# Chip_Tester.net
KiCad netlist of a schematic drawn in Altium Designer
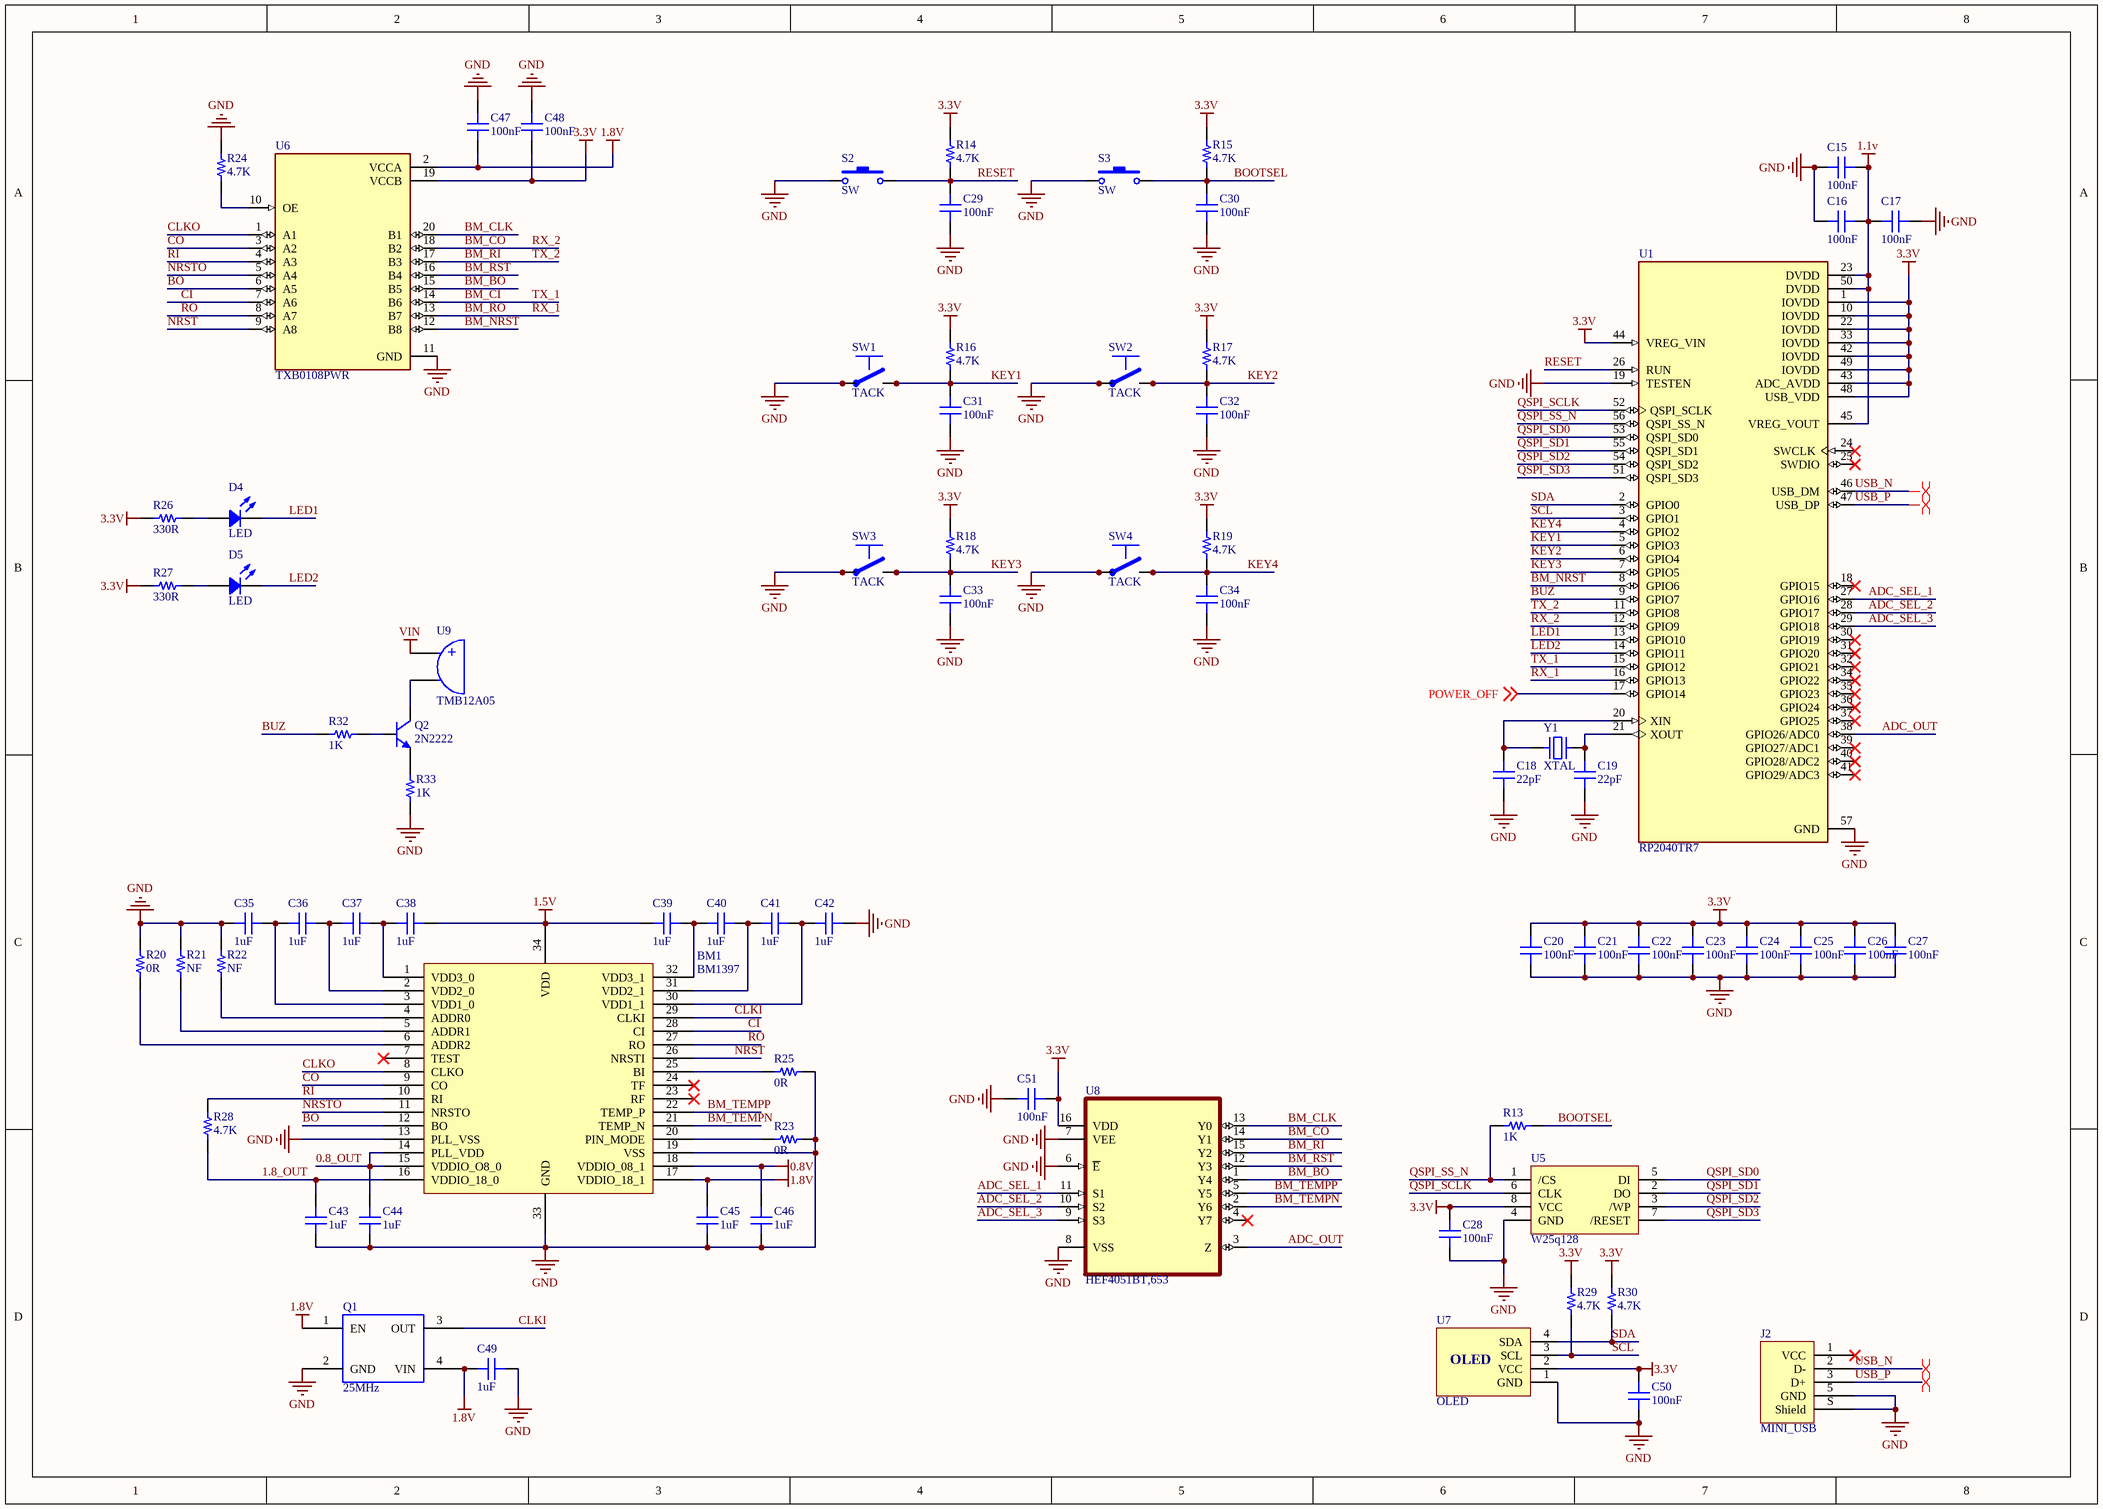
[diagram p0: Chip_Tester.SchDoc]

(export (version "E")
  (design (tool "Eeschema 10.0.6"))
  (components
    (comp (ref "BM1")
      (value "BM1397")
      (footprint "AllSocket")
      (libsource (lib "Chip_Tester") (part "BM1397_0"))
    )
    (comp (ref "C15") (value "100nF") (footprint "CAP_SMD_0805") (libsource (lib "Chip_Tester") (part "CAP")))
    (comp (ref "C16") (value "100nF") (footprint "CAP_SMD_0805") (libsource (lib "Chip_Tester") (part "CAP")))
    (comp (ref "C17") (value "100nF") (footprint "CAP_SMD_0805") (libsource (lib "Chip_Tester") (part "CAP")))
    (comp (ref "C18") (value "22pF") (footprint "CAP_SMD_0805") (libsource (lib "Chip_Tester") (part "CAP")))
    (comp (ref "C19") (value "22pF") (footprint "CAP_SMD_0805") (libsource (lib "Chip_Tester") (part "CAP")))
    (comp (ref "C20") (value "100nF") (footprint "CAP_SMD_0805") (libsource (lib "Chip_Tester") (part "CAP")))
    (comp (ref "C21") (value "100nF") (footprint "CAP_SMD_0805") (libsource (lib "Chip_Tester") (part "CAP")))
    (comp (ref "C22") (value "100nF") (footprint "CAP_SMD_0805") (libsource (lib "Chip_Tester") (part "CAP")))
    (comp (ref "C23") (value "100nF") (footprint "CAP_SMD_0805") (libsource (lib "Chip_Tester") (part "CAP")))
    (comp (ref "C24") (value "100nF") (footprint "CAP_SMD_0805") (libsource (lib "Chip_Tester") (part "CAP")))
    (comp (ref "C25") (value "100nF") (footprint "CAP_SMD_0805") (libsource (lib "Chip_Tester") (part "CAP")))
    (comp (ref "C26") (value "100nF") (footprint "CAP_SMD_0805") (libsource (lib "Chip_Tester") (part "CAP")))
    (comp (ref "C27") (value "100nF") (footprint "CAP_SMD_0805") (libsource (lib "Chip_Tester") (part "CAP")))
    (comp (ref "C28") (value "100nF") (footprint "CAP_SMD_0805") (libsource (lib "Chip_Tester") (part "CAP")))
    (comp (ref "C29") (value "100nF") (footprint "CAP_SMD_0805") (libsource (lib "Chip_Tester") (part "CAP")))
    (comp (ref "C30") (value "100nF") (footprint "CAP_SMD_0805") (libsource (lib "Chip_Tester") (part "CAP")))
    (comp (ref "C31") (value "100nF") (footprint "CAP_SMD_0805") (libsource (lib "Chip_Tester") (part "CAP")))
    (comp (ref "C32") (value "100nF") (footprint "CAP_SMD_0805") (libsource (lib "Chip_Tester") (part "CAP")))
    (comp (ref "C33") (value "100nF") (footprint "CAP_SMD_0805") (libsource (lib "Chip_Tester") (part "CAP")))
    (comp (ref "C34") (value "100nF") (footprint "CAP_SMD_0805") (libsource (lib "Chip_Tester") (part "CAP")))
    (comp (ref "C35") (value "1uF") (footprint "CAP_SMD_0805") (libsource (lib "Chip_Tester") (part "CAP")))
    (comp (ref "C36") (value "1uF") (footprint "CAP_SMD_0805") (libsource (lib "Chip_Tester") (part "CAP")))
    (comp (ref "C37") (value "1uF") (footprint "CAP_SMD_0805") (libsource (lib "Chip_Tester") (part "CAP")))
    (comp (ref "C38") (value "1uF") (footprint "CAP_SMD_0805") (libsource (lib "Chip_Tester") (part "CAP")))
    (comp (ref "C39") (value "1uF") (footprint "CAP_SMD_0805") (libsource (lib "Chip_Tester") (part "CAP")))
    (comp (ref "C40") (value "1uF") (footprint "CAP_SMD_0805") (libsource (lib "Chip_Tester") (part "CAP")))
    (comp (ref "C41") (value "1uF") (footprint "CAP_SMD_0805") (libsource (lib "Chip_Tester") (part "CAP")))
    (comp (ref "C42") (value "1uF") (footprint "CAP_SMD_0805") (libsource (lib "Chip_Tester") (part "CAP")))
    (comp (ref "C43") (value "1uF") (footprint "CAP_SMD_0805") (libsource (lib "Chip_Tester") (part "CAP")))
    (comp (ref "C44") (value "1uF") (footprint "CAP_SMD_0805") (libsource (lib "Chip_Tester") (part "CAP")))
    (comp (ref "C45") (value "1uF") (footprint "CAP_SMD_0805") (libsource (lib "Chip_Tester") (part "CAP")))
    (comp (ref "C46") (value "1uF") (footprint "CAP_SMD_0805") (libsource (lib "Chip_Tester") (part "CAP")))
    (comp (ref "C47") (value "100nF") (footprint "CAP_SMD_0805") (libsource (lib "Chip_Tester") (part "CAP")))
    (comp (ref "C48") (value "100nF") (footprint "CAP_SMD_0805") (libsource (lib "Chip_Tester") (part "CAP")))
    (comp (ref "C49") (value "1uF") (footprint "CAP_SMD_0805") (libsource (lib "Chip_Tester") (part "CAP")))
    (comp (ref "C50") (value "100nF") (footprint "CAP_SMD_0805") (libsource (lib "Chip_Tester") (part "CAP")))
    (comp (ref "C51") (value "100nF") (footprint "CAP_SMD_0805") (libsource (lib "Chip_Tester") (part "CAP")))
    (comp (ref "D4") (value "LED") (footprint "LED_0805_RED") (libsource (lib "Chip_Tester") (part "LED")))
    (comp (ref "D5") (value "LED") (footprint "LED_0805_RED") (libsource (lib "Chip_Tester") (part "LED")))
    (comp (ref "J2")
      (value "MINI_USB")
      (footprint "Mini_usb")
      (libsource (lib "Chip_Tester") (part "MINI_USB"))
    )
    (comp (ref "Q1") (value "25MHz") (footprint "XTALL") (libsource (lib "Chip_Tester") (part "OSCILLATOR")))
    (comp (ref "Q2")
      (value "2N2222")
      (footprint "SOT-23_H")
      (description "NPN General Purpose Amplifier")
      (fields (field (name "MANUFACTURER") "FAIRCHILD") (field (name "MANUFACTURE PART #") "MMBT2222ALT1G"))
      (libsource (lib "Chip_Tester") (part "MMBT2222ALT1G"))
    )
    (comp (ref "R13") (value "1K") (footprint "RES-SMD-0805") (libsource (lib "Chip_Tester") (part "RES")))
    (comp (ref "R14") (value "4.7K") (footprint "RES-SMD-0805") (libsource (lib "Chip_Tester") (part "RES")))
    (comp (ref "R15") (value "4.7K") (footprint "RES-SMD-0805") (libsource (lib "Chip_Tester") (part "RES")))
    (comp (ref "R16") (value "4.7K") (footprint "RES-SMD-0805") (libsource (lib "Chip_Tester") (part "RES")))
    (comp (ref "R17") (value "4.7K") (footprint "RES-SMD-0805") (libsource (lib "Chip_Tester") (part "RES")))
    (comp (ref "R18") (value "4.7K") (footprint "RES-SMD-0805") (libsource (lib "Chip_Tester") (part "RES")))
    (comp (ref "R19") (value "4.7K") (footprint "RES-SMD-0805") (libsource (lib "Chip_Tester") (part "RES")))
    (comp (ref "R20") (value "0R") (footprint "RES-SMD-0805") (libsource (lib "Chip_Tester") (part "RES")))
    (comp (ref "R21") (value "NF") (footprint "RES-SMD-0805") (libsource (lib "Chip_Tester") (part "RES")))
    (comp (ref "R22") (value "NF") (footprint "RES-SMD-0805") (libsource (lib "Chip_Tester") (part "RES")))
    (comp (ref "R23") (value "0R") (footprint "RES-SMD-0805") (libsource (lib "Chip_Tester") (part "RES")))
    (comp (ref "R24") (value "4.7K") (footprint "RES-SMD-0805") (libsource (lib "Chip_Tester") (part "RES")))
    (comp (ref "R25") (value "0R") (footprint "RES-SMD-0805") (libsource (lib "Chip_Tester") (part "RES")))
    (comp (ref "R26") (value "330R") (footprint "RES-SMD-0805") (libsource (lib "Chip_Tester") (part "RES")))
    (comp (ref "R27") (value "330R") (footprint "RES-SMD-0805") (libsource (lib "Chip_Tester") (part "RES")))
    (comp (ref "R28") (value "4.7K") (footprint "RES-SMD-0805") (libsource (lib "Chip_Tester") (part "RES")))
    (comp (ref "R29") (value "4.7K") (footprint "RES-SMD-0805") (libsource (lib "Chip_Tester") (part "RES")))
    (comp (ref "R30") (value "4.7K") (footprint "RES-SMD-0805") (libsource (lib "Chip_Tester") (part "RES")))
    (comp (ref "R32") (value "1K") (footprint "RES-SMD-0805") (libsource (lib "Chip_Tester") (part "RES")))
    (comp (ref "R33") (value "1K") (footprint "RES-SMD-0805") (libsource (lib "Chip_Tester") (part "RES")))
    (comp (ref "S2")
      (value "SW")
      (footprint "SW_PB_SMD_2PIN_SPST_6X3X5")
      (description "SMT Tactile ‎Switch")
      (libsource (lib "Chip_Tester") (part "SW-PB-2Pin-SMD"))
    )
    (comp (ref "S3")
      (value "SW")
      (footprint "SW_PB_SMD_2PIN_SPST_6X3X5")
      (description "SMT Tactile ‎Switch")
      (libsource (lib "Chip_Tester") (part "SW-PB-2Pin-SMD"))
    )
    (comp (ref "SW1") (value "TACK") (footprint "TACK") (libsource (lib "Chip_Tester") (part "SW")))
    (comp (ref "SW2") (value "TACK") (footprint "TACK") (libsource (lib "Chip_Tester") (part "SW")))
    (comp (ref "SW3") (value "TACK") (footprint "TACK") (libsource (lib "Chip_Tester") (part "SW")))
    (comp (ref "SW4") (value "TACK") (footprint "TACK") (libsource (lib "Chip_Tester") (part "SW")))
    (comp (ref "U1")
      (value "RP2040TR7")
      (footprint "RP2040-57N")
      (fields (field (name "MF") "Raspberry Pi"))
      (libsource (lib "Chip_Tester") (part "RP2040TR7"))
    )
    (comp (ref "U5")
      (value "W25q128")
      (footprint "WINBOND SOIC-8")
      (libsource (lib "Chip_Tester") (part "W25q128"))
    )
    (comp (ref "U6")
      (value "TXB0108PWR")
      (footprint "SOP65P640X120-20N")
      (description "8-Bit Bidirectional Voltage-Level Shifter with Auto Direction Sensing and +/-15-kV ESD Protect")
      (fields (field (name "MF") "Texas Instruments") (field (name "DIGI-KEY_PART_NUMBER") "296-21527-2-ND"))
      (libsource (lib "Chip_Tester") (part "TXB0108PWR"))
    )
    (comp (ref "U7") (value "OLED") (footprint "OLED") (libsource (lib "Chip_Tester") (part "OLED")))
    (comp (ref "U8")
      (value "HEF4051BT,653")
      (footprint "SOIC127P600X175-16N")
      (description "4000B Series 3 - 15 V 8-Ch Analog Multiplexer/Demultiplexer - SOIC-16")
      (fields (field (name "MF") "Nexperia USA"))
      (libsource (lib "Chip_Tester") (part "HEF4051BT,653"))
    )
    (comp (ref "U9")
      (value "TMB12A05")
      (footprint "BUZZER_TMB12A05")
      (description "Integrated Buzzer")
      (fields (field (name "MANUFACTURER") "http://www.ehuaxing.com/"))
      (libsource (lib "Chip_Tester") (part "Buzzer_TMB12A05"))
    )
    (comp (ref "Y1")
      (value "XTAL")
      (footprint "XTAL_SMD")
      (description "Crystal 8MHz ±50ppm (Tol) ±50ppm (Stability) 20pF FUND 40Ohm 2-Pin HC-49 Thru-Hole Loose")
      (fields
        (field (name "MANUFACTURER") "IQD")
        (field (name "MANUFACTURER PART NUMBER") "LFXTAL078428BULK")
      )
      (libsource (lib "Chip_Tester") (part "XTAL"))
    )
  )
  (nets
    (net (code "1") (name "/0.8_OUT") (class "Default")
      (node (ref "BM1") (pin "14") (pinfunction "PLL_VDD_14") (pintype "passive"))
      (node (ref "BM1") (pin "15") (pinfunction "VDDIO_O8_0_15") (pintype "passive"))
      (node (ref "C44") (pin "2") (pinfunction "2_2") (pintype "passive"))
    )
    (net (code "2") (name "/1.8_OUT") (class "Default")
      (node (ref "BM1") (pin "16") (pinfunction "VDDIO_18_0_16") (pintype "passive"))
      (node (ref "C43") (pin "2") (pinfunction "2_2") (pintype "passive"))
      (node (ref "R28") (pin "1") (pinfunction "1_1") (pintype "passive"))
    )
    (net (code "3") (name "/ADC_OUT") (class "Default")
      (node (ref "U1") (pin "38") (pinfunction "GPIO26/ADC0_38") (pintype "bidirectional"))
      (node (ref "U8") (pin "3") (pinfunction "Z_3") (pintype "bidirectional"))
    )
    (net (code "4") (name "/ADC_SEL_1") (class "Default")
      (node (ref "U1") (pin "27") (pinfunction "GPIO16_27") (pintype "bidirectional"))
      (node (ref "U8") (pin "11") (pinfunction "S1_11") (pintype "input"))
    )
    (net (code "5") (name "/ADC_SEL_2") (class "Default")
      (node (ref "U1") (pin "28") (pinfunction "GPIO17_28") (pintype "bidirectional"))
      (node (ref "U8") (pin "10") (pinfunction "S2_10") (pintype "input"))
    )
    (net (code "6") (name "/ADC_SEL_3") (class "Default")
      (node (ref "U1") (pin "29") (pinfunction "GPIO18_29") (pintype "bidirectional"))
      (node (ref "U8") (pin "9") (pinfunction "S3_9") (pintype "input"))
    )
    (net (code "7") (name "/BM_BO") (class "Default")
      (node (ref "U6") (pin "15") (pinfunction "B5_15") (pintype "bidirectional"))
      (node (ref "U8") (pin "1") (pinfunction "Y4_1") (pintype "bidirectional"))
    )
    (net (code "8") (name "/BM_CI") (class "Default")
      (node (ref "U1") (pin "15") (pinfunction "GPIO12_15") (pintype "bidirectional"))
      (node (ref "U6") (pin "14") (pinfunction "B6_14") (pintype "bidirectional"))
    )
    (net (code "9") (name "/BM_CLK") (class "Default")
      (node (ref "U6") (pin "20") (pinfunction "B1_20") (pintype "bidirectional"))
      (node (ref "U8") (pin "13") (pinfunction "Y0_13") (pintype "bidirectional"))
    )
    (net (code "10") (name "/BM_CO") (class "Default")
      (node (ref "U1") (pin "12") (pinfunction "GPIO9_12") (pintype "bidirectional"))
      (node (ref "U6") (pin "18") (pinfunction "B2_18") (pintype "bidirectional"))
      (node (ref "U8") (pin "14") (pinfunction "Y1_14") (pintype "bidirectional"))
    )
    (net (code "11") (name "/BM_NRST") (class "Default")
      (node (ref "U1") (pin "8") (pinfunction "GPIO6_8") (pintype "bidirectional"))
      (node (ref "U6") (pin "12") (pinfunction "B8_12") (pintype "bidirectional"))
    )
    (net (code "12") (name "/BM_RI") (class "Default")
      (node (ref "U1") (pin "11") (pinfunction "GPIO8_11") (pintype "bidirectional"))
      (node (ref "U6") (pin "17") (pinfunction "B3_17") (pintype "bidirectional"))
      (node (ref "U8") (pin "15") (pinfunction "Y2_15") (pintype "bidirectional"))
    )
    (net (code "13") (name "/BM_RO") (class "Default")
      (node (ref "U1") (pin "16") (pinfunction "GPIO13_16") (pintype "bidirectional"))
      (node (ref "U6") (pin "13") (pinfunction "B7_13") (pintype "bidirectional"))
    )
    (net (code "14") (name "/BM_RST") (class "Default")
      (node (ref "U6") (pin "16") (pinfunction "B4_16") (pintype "bidirectional"))
      (node (ref "U8") (pin "12") (pinfunction "Y3_12") (pintype "bidirectional"))
    )
    (net (code "15") (name "/BM_TEMPN") (class "Default")
      (node (ref "BM1") (pin "21") (pinfunction "TEMP_N_21") (pintype "passive"))
      (node (ref "U8") (pin "2") (pinfunction "Y6_2") (pintype "bidirectional"))
    )
    (net (code "16") (name "/BM_TEMPP") (class "Default")
      (node (ref "BM1") (pin "22") (pinfunction "TEMP_P_22") (pintype "passive"))
      (node (ref "U8") (pin "5") (pinfunction "Y5_5") (pintype "bidirectional"))
    )
    (net (code "17") (name "/BO") (class "Default")
      (node (ref "BM1") (pin "12") (pinfunction "BO_12") (pintype "passive"))
      (node (ref "U6") (pin "6") (pinfunction "A5_6") (pintype "bidirectional"))
    )
    (net (code "18") (name "/BOOTSEL") (class "Default")
      (node (ref "C30") (pin "2") (pinfunction "2_2") (pintype "passive"))
      (node (ref "R13") (pin "2") (pinfunction "2_2") (pintype "passive"))
      (node (ref "R15") (pin "1") (pinfunction "1_1") (pintype "passive"))
      (node (ref "S3") (pin "2") (pinfunction "2_2") (pintype "passive"))
    )
    (net (code "19") (name "/BUZ") (class "Default")
      (node (ref "R32") (pin "1") (pinfunction "1_1") (pintype "passive"))
      (node (ref "U1") (pin "9") (pinfunction "GPIO7_9") (pintype "bidirectional"))
    )
    (net (code "20") (name "/CI") (class "Default")
      (node (ref "BM1") (pin "28") (pinfunction "CI_28") (pintype "passive"))
      (node (ref "U6") (pin "7") (pinfunction "A6_7") (pintype "bidirectional"))
    )
    (net (code "21") (name "/CLKI") (class "Default")
      (node (ref "BM1") (pin "29") (pinfunction "CLKI_29") (pintype "passive"))
      (node (ref "Q1") (pin "3") (pinfunction "OUT_3") (pintype "passive"))
    )
    (net (code "22") (name "/CLKO") (class "Default")
      (node (ref "BM1") (pin "8") (pinfunction "CLKO_8") (pintype "passive"))
      (node (ref "U6") (pin "1") (pinfunction "A1_1") (pintype "bidirectional"))
    )
    (net (code "23") (name "/CO") (class "Default")
      (node (ref "BM1") (pin "9") (pinfunction "CO_9") (pintype "passive"))
      (node (ref "U6") (pin "3") (pinfunction "A2_3") (pintype "bidirectional"))
    )
    (net (code "24") (name "/KEY1") (class "Default")
      (node (ref "C31") (pin "2") (pinfunction "2_2") (pintype "passive"))
      (node (ref "R16") (pin "1") (pinfunction "1_1") (pintype "passive"))
      (node (ref "SW1") (pin "3") (pinfunction "2_3") (pintype "passive"))
      (node (ref "SW1") (pin "4") (pinfunction "2_4") (pintype "passive"))
      (node (ref "U1") (pin "5") (pinfunction "GPIO3_5") (pintype "bidirectional"))
    )
    (net (code "25") (name "/KEY2") (class "Default")
      (node (ref "C32") (pin "2") (pinfunction "2_2") (pintype "passive"))
      (node (ref "R17") (pin "1") (pinfunction "1_1") (pintype "passive"))
      (node (ref "SW2") (pin "3") (pinfunction "2_3") (pintype "passive"))
      (node (ref "SW2") (pin "4") (pinfunction "2_4") (pintype "passive"))
      (node (ref "U1") (pin "6") (pinfunction "GPIO4_6") (pintype "bidirectional"))
    )
    (net (code "26") (name "/KEY3") (class "Default")
      (node (ref "C33") (pin "2") (pinfunction "2_2") (pintype "passive"))
      (node (ref "R18") (pin "1") (pinfunction "1_1") (pintype "passive"))
      (node (ref "SW3") (pin "3") (pinfunction "2_3") (pintype "passive"))
      (node (ref "SW3") (pin "4") (pinfunction "2_4") (pintype "passive"))
      (node (ref "U1") (pin "7") (pinfunction "GPIO5_7") (pintype "bidirectional"))
    )
    (net (code "27") (name "/KEY4") (class "Default")
      (node (ref "C34") (pin "2") (pinfunction "2_2") (pintype "passive"))
      (node (ref "R19") (pin "1") (pinfunction "1_1") (pintype "passive"))
      (node (ref "SW4") (pin "3") (pinfunction "2_3") (pintype "passive"))
      (node (ref "SW4") (pin "4") (pinfunction "2_4") (pintype "passive"))
      (node (ref "U1") (pin "4") (pinfunction "GPIO2_4") (pintype "bidirectional"))
    )
    (net (code "28") (name "/LED1") (class "Default")
      (node (ref "D4") (pin "2") (pinfunction "2_2") (pintype "passive"))
      (node (ref "U1") (pin "13") (pinfunction "GPIO10_13") (pintype "bidirectional"))
    )
    (net (code "29") (name "/LED2") (class "Default")
      (node (ref "D5") (pin "2") (pinfunction "2_2") (pintype "passive"))
      (node (ref "U1") (pin "14") (pinfunction "GPIO11_14") (pintype "bidirectional"))
    )
    (net (code "30") (name "/NRST") (class "Default")
      (node (ref "BM1") (pin "26") (pinfunction "NRSTI_26") (pintype "passive"))
      (node (ref "U6") (pin "9") (pinfunction "A8_9") (pintype "bidirectional"))
    )
    (net (code "31") (name "/NRSTO") (class "Default")
      (node (ref "BM1") (pin "11") (pinfunction "NRSTO_11") (pintype "passive"))
      (node (ref "U6") (pin "5") (pinfunction "A4_5") (pintype "bidirectional"))
    )
    (net (code "32") (name "/QSPI_SCLK") (class "Default")
      (node (ref "U1") (pin "52") (pinfunction "QSPI_SCLK_52") (pintype "bidirectional"))
      (node (ref "U5") (pin "6") (pinfunction "CLK_6") (pintype "passive"))
    )
    (net (code "33") (name "/QSPI_SD0") (class "Default")
      (node (ref "U1") (pin "53") (pinfunction "QSPI_SD0_53") (pintype "bidirectional"))
      (node (ref "U5") (pin "5") (pinfunction "DI_5") (pintype "passive"))
    )
    (net (code "34") (name "/QSPI_SD1") (class "Default")
      (node (ref "U1") (pin "55") (pinfunction "QSPI_SD1_55") (pintype "bidirectional"))
      (node (ref "U5") (pin "2") (pinfunction "DO_2") (pintype "passive"))
    )
    (net (code "35") (name "/QSPI_SD2") (class "Default")
      (node (ref "U1") (pin "54") (pinfunction "QSPI_SD2_54") (pintype "bidirectional"))
      (node (ref "U5") (pin "3") (pinfunction "/WP_3") (pintype "passive"))
    )
    (net (code "36") (name "/QSPI_SD3") (class "Default")
      (node (ref "U1") (pin "51") (pinfunction "QSPI_SD3_51") (pintype "bidirectional"))
      (node (ref "U5") (pin "7") (pinfunction "/RESET_7") (pintype "passive"))
    )
    (net (code "37") (name "/QSPI_SS_N") (class "Default")
      (node (ref "R13") (pin "1") (pinfunction "1_1") (pintype "passive"))
      (node (ref "U1") (pin "56") (pinfunction "QSPI_SS_N_56") (pintype "bidirectional"))
      (node (ref "U5") (pin "1") (pinfunction "/CS_1") (pintype "passive"))
    )
    (net (code "38") (name "/RESET") (class "Default")
      (node (ref "C29") (pin "2") (pinfunction "2_2") (pintype "passive"))
      (node (ref "R14") (pin "1") (pinfunction "1_1") (pintype "passive"))
      (node (ref "S2") (pin "2") (pinfunction "2_2") (pintype "passive"))
      (node (ref "U1") (pin "26") (pinfunction "RUN_26") (pintype "input"))
    )
    (net (code "39") (name "/RI") (class "Default")
      (node (ref "BM1") (pin "10") (pinfunction "RI_10") (pintype "passive"))
      (node (ref "R28") (pin "2") (pinfunction "2_2") (pintype "passive"))
      (node (ref "U6") (pin "4") (pinfunction "A3_4") (pintype "bidirectional"))
    )
    (net (code "40") (name "/RO") (class "Default")
      (node (ref "BM1") (pin "27") (pinfunction "RO_27") (pintype "passive"))
      (node (ref "U6") (pin "8") (pinfunction "A7_8") (pintype "bidirectional"))
    )
    (net (code "41") (name "/SCL") (class "Default")
      (node (ref "R29") (pin "1") (pinfunction "1_1") (pintype "passive"))
      (node (ref "U1") (pin "3") (pinfunction "GPIO1_3") (pintype "bidirectional"))
      (node (ref "U7") (pin "3") (pinfunction "SCL_3") (pintype "passive"))
    )
    (net (code "42") (name "/SDA") (class "Default")
      (node (ref "R30") (pin "1") (pinfunction "1_1") (pintype "passive"))
      (node (ref "U1") (pin "2") (pinfunction "GPIO0_2") (pintype "bidirectional"))
      (node (ref "U7") (pin "4") (pinfunction "SDA_4") (pintype "passive"))
    )
    (net (code "43") (name "/USB_N") (class "Default")
      (node (ref "J2") (pin "2") (pinfunction "D-_2") (pintype "passive"))
      (node (ref "U1") (pin "46") (pinfunction "USB_DM_46") (pintype "bidirectional"))
    )
    (net (code "44") (name "/USB_P") (class "Default")
      (node (ref "J2") (pin "3") (pinfunction "D+_3") (pintype "passive"))
      (node (ref "U1") (pin "47") (pinfunction "USB_DP_47") (pintype "bidirectional"))
    )
    (net (code "45") (name "0.8V") (class "Default")
      (node (ref "BM1") (pin "18") (pinfunction "VDDIO_08_1_18") (pintype "passive"))
      (node (ref "C46") (pin "2") (pinfunction "2_2") (pintype "passive"))
    )
    (net (code "46") (name "1.1v") (class "Default")
      (node (ref "C15") (pin "2") (pinfunction "2_2") (pintype "passive"))
      (node (ref "C16") (pin "2") (pinfunction "2_2") (pintype "passive"))
      (node (ref "C17") (pin "1") (pinfunction "1_1") (pintype "passive"))
      (node (ref "U1") (pin "23") (pinfunction "DVDD_23") (pintype "power_in"))
      (node (ref "U1") (pin "45") (pinfunction "VREG_VOUT_45") (pintype "passive"))
      (node (ref "U1") (pin "50") (pinfunction "DVDD_50") (pintype "power_in"))
    )
    (net (code "47") (name "1.5V") (class "Default")
      (node (ref "BM1") (pin "34") (pinfunction "VDD_34") (pintype "passive"))
      (node (ref "C38") (pin "2") (pinfunction "2_2") (pintype "passive"))
      (node (ref "C39") (pin "1") (pinfunction "1_1") (pintype "passive"))
    )
    (net (code "48") (name "1.8V") (class "Default")
      (node (ref "BM1") (pin "17") (pinfunction "VDDIO_18_1_17") (pintype "passive"))
      (node (ref "C45") (pin "2") (pinfunction "2_2") (pintype "passive"))
      (node (ref "C47") (pin "1") (pinfunction "1_1") (pintype "passive"))
      (node (ref "C49") (pin "2") (pinfunction "2_2") (pintype "passive"))
      (node (ref "Q1") (pin "1") (pinfunction "EN_1") (pintype "passive"))
      (node (ref "Q1") (pin "4") (pinfunction "VIN_4") (pintype "passive"))
      (node (ref "U6") (pin "2") (pinfunction "VCCA_2") (pintype "power_in"))
    )
    (net (code "49") (name "3.3V") (class "Default")
      (node (ref "C20") (pin "1") (pinfunction "1_1") (pintype "passive"))
      (node (ref "C21") (pin "1") (pinfunction "1_1") (pintype "passive"))
      (node (ref "C22") (pin "1") (pinfunction "1_1") (pintype "passive"))
      (node (ref "C23") (pin "1") (pinfunction "1_1") (pintype "passive"))
      (node (ref "C24") (pin "1") (pinfunction "1_1") (pintype "passive"))
      (node (ref "C25") (pin "1") (pinfunction "1_1") (pintype "passive"))
      (node (ref "C26") (pin "1") (pinfunction "1_1") (pintype "passive"))
      (node (ref "C27") (pin "1") (pinfunction "1_1") (pintype "passive"))
      (node (ref "C28") (pin "1") (pinfunction "1_1") (pintype "passive"))
      (node (ref "C48") (pin "1") (pinfunction "1_1") (pintype "passive"))
      (node (ref "C50") (pin "2") (pinfunction "2_2") (pintype "passive"))
      (node (ref "C51") (pin "2") (pinfunction "2_2") (pintype "passive"))
      (node (ref "R14") (pin "2") (pinfunction "2_2") (pintype "passive"))
      (node (ref "R15") (pin "2") (pinfunction "2_2") (pintype "passive"))
      (node (ref "R16") (pin "2") (pinfunction "2_2") (pintype "passive"))
      (node (ref "R17") (pin "2") (pinfunction "2_2") (pintype "passive"))
      (node (ref "R18") (pin "2") (pinfunction "2_2") (pintype "passive"))
      (node (ref "R19") (pin "2") (pinfunction "2_2") (pintype "passive"))
      (node (ref "R26") (pin "2") (pinfunction "2_2") (pintype "passive"))
      (node (ref "R27") (pin "2") (pinfunction "2_2") (pintype "passive"))
      (node (ref "R29") (pin "2") (pinfunction "2_2") (pintype "passive"))
      (node (ref "R30") (pin "2") (pinfunction "2_2") (pintype "passive"))
      (node (ref "U1") (pin "1") (pinfunction "IOVDD_1") (pintype "power_in"))
      (node (ref "U1") (pin "10") (pinfunction "IOVDD_10") (pintype "power_in"))
      (node (ref "U1") (pin "22") (pinfunction "IOVDD_22") (pintype "power_in"))
      (node (ref "U1") (pin "33") (pinfunction "IOVDD_33") (pintype "power_in"))
      (node (ref "U1") (pin "42") (pinfunction "IOVDD_42") (pintype "power_in"))
      (node (ref "U1") (pin "43") (pinfunction "ADC_AVDD_43") (pintype "power_in"))
      (node (ref "U1") (pin "44") (pinfunction "VREG_VIN_44") (pintype "input"))
      (node (ref "U1") (pin "48") (pinfunction "USB_VDD_48") (pintype "power_in"))
      (node (ref "U1") (pin "49") (pinfunction "IOVDD_49") (pintype "power_in"))
      (node (ref "U5") (pin "8") (pinfunction "VCC_8") (pintype "passive"))
      (node (ref "U6") (pin "19") (pinfunction "VCCB_19") (pintype "power_in"))
      (node (ref "U7") (pin "2") (pinfunction "VCC_2") (pintype "passive"))
      (node (ref "U8") (pin "16") (pinfunction "VDD_16") (pintype "power_in"))
    )
    (net (code "50") (name "GND") (class "Default")
      (node (ref "BM1") (pin "13") (pinfunction "PLL_VSS_13") (pintype "passive"))
      (node (ref "BM1") (pin "19") (pinfunction "VSS_19") (pintype "passive"))
      (node (ref "BM1") (pin "33") (pinfunction "GND_33") (pintype "passive"))
      (node (ref "C15") (pin "1") (pinfunction "1_1") (pintype "passive"))
      (node (ref "C16") (pin "1") (pinfunction "1_1") (pintype "passive"))
      (node (ref "C17") (pin "2") (pinfunction "2_2") (pintype "passive"))
      (node (ref "C18") (pin "2") (pinfunction "2_2") (pintype "passive"))
      (node (ref "C19") (pin "2") (pinfunction "2_2") (pintype "passive"))
      (node (ref "C20") (pin "2") (pinfunction "2_2") (pintype "passive"))
      (node (ref "C21") (pin "2") (pinfunction "2_2") (pintype "passive"))
      (node (ref "C22") (pin "2") (pinfunction "2_2") (pintype "passive"))
      (node (ref "C23") (pin "2") (pinfunction "2_2") (pintype "passive"))
      (node (ref "C24") (pin "2") (pinfunction "2_2") (pintype "passive"))
      (node (ref "C25") (pin "2") (pinfunction "2_2") (pintype "passive"))
      (node (ref "C26") (pin "2") (pinfunction "2_2") (pintype "passive"))
      (node (ref "C27") (pin "2") (pinfunction "2_2") (pintype "passive"))
      (node (ref "C28") (pin "2") (pinfunction "2_2") (pintype "passive"))
      (node (ref "C29") (pin "1") (pinfunction "1_1") (pintype "passive"))
      (node (ref "C30") (pin "1") (pinfunction "1_1") (pintype "passive"))
      (node (ref "C31") (pin "1") (pinfunction "1_1") (pintype "passive"))
      (node (ref "C32") (pin "1") (pinfunction "1_1") (pintype "passive"))
      (node (ref "C33") (pin "1") (pinfunction "1_1") (pintype "passive"))
      (node (ref "C34") (pin "1") (pinfunction "1_1") (pintype "passive"))
      (node (ref "C35") (pin "1") (pinfunction "1_1") (pintype "passive"))
      (node (ref "C42") (pin "2") (pinfunction "2_2") (pintype "passive"))
      (node (ref "C43") (pin "1") (pinfunction "1_1") (pintype "passive"))
      (node (ref "C44") (pin "1") (pinfunction "1_1") (pintype "passive"))
      (node (ref "C45") (pin "1") (pinfunction "1_1") (pintype "passive"))
      (node (ref "C46") (pin "1") (pinfunction "1_1") (pintype "passive"))
      (node (ref "C47") (pin "2") (pinfunction "2_2") (pintype "passive"))
      (node (ref "C48") (pin "2") (pinfunction "2_2") (pintype "passive"))
      (node (ref "C49") (pin "1") (pinfunction "1_1") (pintype "passive"))
      (node (ref "C50") (pin "1") (pinfunction "1_1") (pintype "passive"))
      (node (ref "C51") (pin "1") (pinfunction "1_1") (pintype "passive"))
      (node (ref "J2") (pin "5") (pinfunction "GND_5") (pintype "passive"))
      (node (ref "J2") (pin "S") (pinfunction "Shield_S") (pintype "passive"))
      (node (ref "Q1") (pin "2") (pinfunction "GND_2") (pintype "passive"))
      (node (ref "R20") (pin "2") (pinfunction "2_2") (pintype "passive"))
      (node (ref "R21") (pin "2") (pinfunction "2_2") (pintype "passive"))
      (node (ref "R22") (pin "2") (pinfunction "2_2") (pintype "passive"))
      (node (ref "R23") (pin "1") (pinfunction "1_1") (pintype "passive"))
      (node (ref "R24") (pin "2") (pinfunction "2_2") (pintype "passive"))
      (node (ref "R25") (pin "1") (pinfunction "1_1") (pintype "passive"))
      (node (ref "R33") (pin "2") (pinfunction "2_2") (pintype "passive"))
      (node (ref "S2") (pin "1") (pinfunction "1_1") (pintype "passive"))
      (node (ref "S3") (pin "1") (pinfunction "1_1") (pintype "passive"))
      (node (ref "SW1") (pin "1") (pinfunction "1_1") (pintype "passive"))
      (node (ref "SW1") (pin "2") (pinfunction "1_2") (pintype "passive"))
      (node (ref "SW2") (pin "1") (pinfunction "1_1") (pintype "passive"))
      (node (ref "SW2") (pin "2") (pinfunction "1_2") (pintype "passive"))
      (node (ref "SW3") (pin "1") (pinfunction "1_1") (pintype "passive"))
      (node (ref "SW3") (pin "2") (pinfunction "1_2") (pintype "passive"))
      (node (ref "SW4") (pin "1") (pinfunction "1_1") (pintype "passive"))
      (node (ref "SW4") (pin "2") (pinfunction "1_2") (pintype "passive"))
      (node (ref "U1") (pin "19") (pinfunction "TESTEN_19") (pintype "input"))
      (node (ref "U1") (pin "57") (pinfunction "GND_57") (pintype "power_in"))
      (node (ref "U5") (pin "4") (pinfunction "GND_4") (pintype "passive"))
      (node (ref "U6") (pin "11") (pinfunction "GND_11") (pintype "power_in"))
      (node (ref "U7") (pin "1") (pinfunction "GND_1") (pintype "passive"))
      (node (ref "U8") (pin "6") (pinfunction "~{E}_6") (pintype "input"))
      (node (ref "U8") (pin "7") (pinfunction "VEE_7") (pintype "power_in"))
      (node (ref "U8") (pin "8") (pinfunction "VSS_8") (pintype "passive"))
    )
    (net (code "51") (name "Net-(BM1-ADDR0)") (class "Default")
      (node (ref "BM1") (pin "4") (pinfunction "ADDR0_4") (pintype "passive"))
      (node (ref "R22") (pin "1") (pinfunction "1_1") (pintype "passive"))
    )
    (net (code "52") (name "Net-(BM1-ADDR1)") (class "Default")
      (node (ref "BM1") (pin "5") (pinfunction "ADDR1_5") (pintype "passive"))
      (node (ref "R21") (pin "1") (pinfunction "1_1") (pintype "passive"))
    )
    (net (code "53") (name "Net-(BM1-ADDR2)") (class "Default")
      (node (ref "BM1") (pin "6") (pinfunction "ADDR2_6") (pintype "passive"))
      (node (ref "R20") (pin "1") (pinfunction "1_1") (pintype "passive"))
    )
    (net (code "54") (name "Net-(BM1-BI)") (class "Default")
      (node (ref "BM1") (pin "25") (pinfunction "BI_25") (pintype "passive"))
      (node (ref "R25") (pin "2") (pinfunction "2_2") (pintype "passive"))
    )
    (net (code "55") (name "Net-(BM1-PIN_MODE)") (class "Default")
      (node (ref "BM1") (pin "20") (pinfunction "PIN_MODE_20") (pintype "passive"))
      (node (ref "R23") (pin "2") (pinfunction "2_2") (pintype "passive"))
    )
    (net (code "56") (name "Net-(BM1-VDD1_0)") (class "Default")
      (node (ref "BM1") (pin "3") (pinfunction "VDD1_0_3") (pintype "passive"))
      (node (ref "C35") (pin "2") (pinfunction "2_2") (pintype "passive"))
      (node (ref "C36") (pin "1") (pinfunction "1_1") (pintype "passive"))
    )
    (net (code "57") (name "Net-(BM1-VDD1_1)") (class "Default")
      (node (ref "BM1") (pin "30") (pinfunction "VDD1_1_30") (pintype "passive"))
      (node (ref "C41") (pin "2") (pinfunction "2_2") (pintype "passive"))
      (node (ref "C42") (pin "1") (pinfunction "1_1") (pintype "passive"))
    )
    (net (code "58") (name "Net-(BM1-VDD2_0)") (class "Default")
      (node (ref "BM1") (pin "2") (pinfunction "VDD2_0_2") (pintype "passive"))
      (node (ref "C36") (pin "2") (pinfunction "2_2") (pintype "passive"))
      (node (ref "C37") (pin "1") (pinfunction "1_1") (pintype "passive"))
    )
    (net (code "59") (name "Net-(BM1-VDD2_1)") (class "Default")
      (node (ref "BM1") (pin "31") (pinfunction "VDD2_1_31") (pintype "passive"))
      (node (ref "C40") (pin "2") (pinfunction "2_2") (pintype "passive"))
      (node (ref "C41") (pin "1") (pinfunction "1_1") (pintype "passive"))
    )
    (net (code "60") (name "Net-(BM1-VDD3_0)") (class "Default")
      (node (ref "BM1") (pin "1") (pinfunction "VDD3_0_1") (pintype "passive"))
      (node (ref "C37") (pin "2") (pinfunction "2_2") (pintype "passive"))
      (node (ref "C38") (pin "1") (pinfunction "1_1") (pintype "passive"))
    )
    (net (code "61") (name "Net-(BM1-VDD3_1)") (class "Default")
      (node (ref "BM1") (pin "32") (pinfunction "VDD3_1_32") (pintype "passive"))
      (node (ref "C39") (pin "2") (pinfunction "2_2") (pintype "passive"))
      (node (ref "C40") (pin "1") (pinfunction "1_1") (pintype "passive"))
    )
    (net (code "62") (name "Net-(D4-Pad1)") (class "Default")
      (node (ref "D4") (pin "1") (pinfunction "1_1") (pintype "passive"))
      (node (ref "R26") (pin "1") (pinfunction "1_1") (pintype "passive"))
    )
    (net (code "63") (name "Net-(D5-Pad1)") (class "Default")
      (node (ref "D5") (pin "1") (pinfunction "1_1") (pintype "passive"))
      (node (ref "R27") (pin "1") (pinfunction "1_1") (pintype "passive"))
    )
    (net (code "64") (name "Net-(Q2-B)") (class "Default")
      (node (ref "Q2") (pin "1") (pinfunction "B_1") (pintype "passive"))
      (node (ref "R32") (pin "2") (pinfunction "2_2") (pintype "passive"))
    )
    (net (code "65") (name "Net-(Q2-C)") (class "Default")
      (node (ref "Q2") (pin "3") (pinfunction "C_3") (pintype "passive"))
      (node (ref "U9") (pin "2") (pinfunction "2_2") (pintype "passive"))
    )
    (net (code "66") (name "Net-(Q2-E)") (class "Default")
      (node (ref "Q2") (pin "2") (pinfunction "E_2") (pintype "passive"))
      (node (ref "R33") (pin "1") (pinfunction "1_1") (pintype "passive"))
    )
    (net (code "67") (name "Net-(U1-XIN)") (class "Default")
      (node (ref "C18") (pin "1") (pinfunction "1_1") (pintype "passive"))
      (node (ref "U1") (pin "20") (pinfunction "XIN_20") (pintype "input"))
      (node (ref "Y1") (pin "1") (pinfunction "1_1") (pintype "passive"))
    )
    (net (code "68") (name "Net-(U1-XOUT)") (class "Default")
      (node (ref "C19") (pin "1") (pinfunction "1_1") (pintype "passive"))
      (node (ref "U1") (pin "21") (pinfunction "XOUT_21") (pintype "output"))
      (node (ref "Y1") (pin "2") (pinfunction "2_2") (pintype "passive"))
    )
    (net (code "69") (name "Net-(U6-OE)") (class "Default")
      (node (ref "R24") (pin "1") (pinfunction "1_1") (pintype "passive"))
      (node (ref "U6") (pin "10") (pinfunction "OE_10") (pintype "input"))
    )
    (net (code "70") (name "POWER_OFF") (class "Default")
      (node (ref "U1") (pin "17") (pinfunction "GPIO14_17") (pintype "bidirectional"))
    )
    (net (code "71") (name "VIN") (class "Default")
      (node (ref "U9") (pin "1") (pinfunction "1_1") (pintype "passive"))
    )
    (net (code "72") (name "unconnected-(BM1-RF-Pad23)") (class "Default")
      (node (ref "BM1") (pin "23") (pinfunction "RF_23") (pintype "passive+no_connect"))
    )
    (net (code "73") (name "unconnected-(BM1-TEST-Pad7)") (class "Default")
      (node (ref "BM1") (pin "7") (pinfunction "TEST_7") (pintype "passive+no_connect"))
    )
    (net (code "74") (name "unconnected-(BM1-TF-Pad24)") (class "Default")
      (node (ref "BM1") (pin "24") (pinfunction "TF_24") (pintype "passive+no_connect"))
    )
    (net (code "75") (name "unconnected-(J2-VCC-Pad1)") (class "Default")
      (node (ref "J2") (pin "1") (pinfunction "VCC_1") (pintype "passive+no_connect"))
    )
    (net (code "76") (name "unconnected-(U1-GPIO15-Pad18)") (class "Default")
      (node (ref "U1") (pin "18") (pinfunction "GPIO15_18") (pintype "bidirectional+no_connect"))
    )
    (net (code "77") (name "unconnected-(U1-GPIO19-Pad30)") (class "Default")
      (node (ref "U1") (pin "30") (pinfunction "GPIO19_30") (pintype "bidirectional+no_connect"))
    )
    (net (code "78") (name "unconnected-(U1-GPIO20-Pad31)") (class "Default")
      (node (ref "U1") (pin "31") (pinfunction "GPIO20_31") (pintype "bidirectional+no_connect"))
    )
    (net (code "79") (name "unconnected-(U1-GPIO21-Pad32)") (class "Default")
      (node (ref "U1") (pin "32") (pinfunction "GPIO21_32") (pintype "bidirectional+no_connect"))
    )
    (net (code "80") (name "unconnected-(U1-GPIO22-Pad34)") (class "Default")
      (node (ref "U1") (pin "34") (pinfunction "GPIO22_34") (pintype "bidirectional+no_connect"))
    )
    (net (code "81") (name "unconnected-(U1-GPIO23-Pad35)") (class "Default")
      (node (ref "U1") (pin "35") (pinfunction "GPIO23_35") (pintype "bidirectional+no_connect"))
    )
    (net (code "82") (name "unconnected-(U1-GPIO24-Pad36)") (class "Default")
      (node (ref "U1") (pin "36") (pinfunction "GPIO24_36") (pintype "bidirectional+no_connect"))
    )
    (net (code "83") (name "unconnected-(U1-GPIO25-Pad37)") (class "Default")
      (node (ref "U1") (pin "37") (pinfunction "GPIO25_37") (pintype "bidirectional+no_connect"))
    )
    (net (code "84") (name "unconnected-(U1-GPIO27{slash}ADC1-Pad39)") (class "Default")
      (node (ref "U1") (pin "39") (pinfunction "GPIO27/ADC1_39") (pintype "bidirectional+no_connect"))
    )
    (net (code "85") (name "unconnected-(U1-GPIO28{slash}ADC2-Pad40)") (class "Default")
      (node (ref "U1") (pin "40") (pinfunction "GPIO28/ADC2_40") (pintype "bidirectional+no_connect"))
    )
    (net (code "86") (name "unconnected-(U1-GPIO29{slash}ADC3-Pad41)") (class "Default")
      (node (ref "U1") (pin "41") (pinfunction "GPIO29/ADC3_41") (pintype "bidirectional+no_connect"))
    )
    (net (code "87") (name "unconnected-(U1-SWCLK-Pad24)") (class "Default")
      (node (ref "U1") (pin "24") (pinfunction "SWCLK_24") (pintype "input+no_connect"))
    )
    (net (code "88") (name "unconnected-(U1-SWDIO-Pad25)") (class "Default")
      (node (ref "U1") (pin "25") (pinfunction "SWDIO_25") (pintype "bidirectional+no_connect"))
    )
    (net (code "89") (name "unconnected-(U8-Y7-Pad4)") (class "Default")
      (node (ref "U8") (pin "4") (pinfunction "Y7_4") (pintype "bidirectional+no_connect"))
    )
  )
)
